# Nucleo_Mouse_SensorBoard_v2.net
KiCad netlist of a schematic drawn in EAGLE
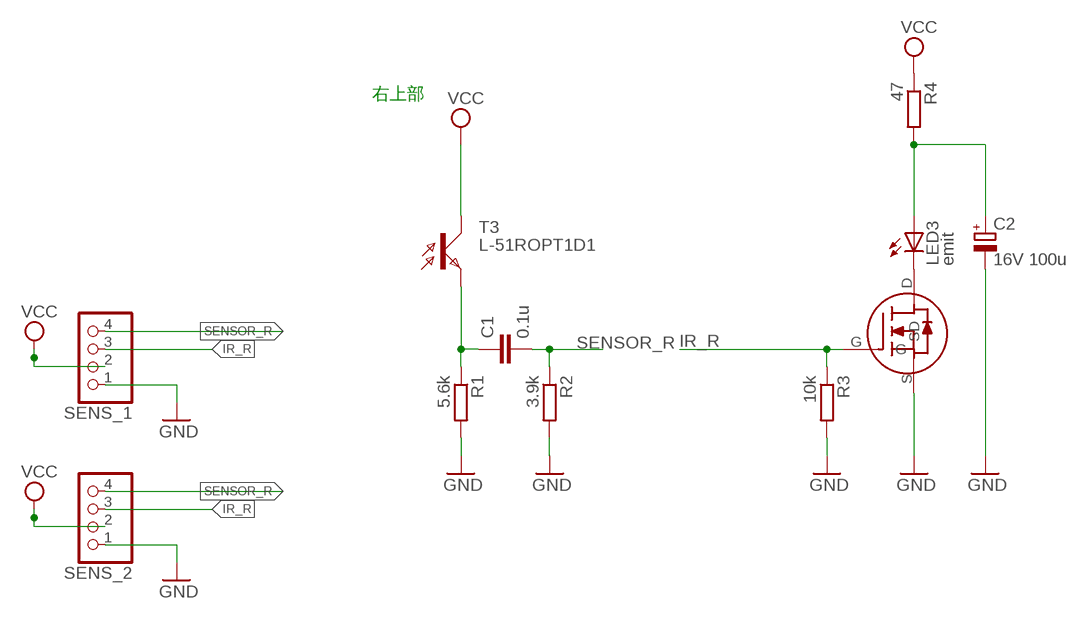
[diagram p0: schematic, sheet 1]

(export (version "E")
  (design (tool "Eeschema 10.0.6"))
  (components
    (comp (ref "2N2")
      (value "2N7000")
      (footprint "eagle-import:2N7000")
      (libsource (lib "eagle-import") (part "2N7000"))
    )
    (comp (ref "C1")
      (value "0.1u")
      (footprint "eagle-import:C2.5-3")
      (libsource (lib "eagle-import") (part "C2,5-3"))
    )
    (comp (ref "C2")
      (value "16V 100u")
      (footprint "eagle-import:E2-4")
      (libsource (lib "eagle-import") (part "CPOL-EUE2-4"))
    )
    (comp (ref "LED3")
      (value "emit")
      (footprint "eagle-import:LED5MM")
      (libsource (lib "eagle-import") (part "LED5MM"))
    )
    (comp (ref "R1")
      (value "5.6k")
      (footprint "eagle-import:0204_7")
      (libsource (lib "eagle-import") (part "R-EU_0204/7"))
    )
    (comp (ref "R2")
      (value "3.9k")
      (footprint "eagle-import:0204_7")
      (libsource (lib "eagle-import") (part "R-EU_0204/7"))
    )
    (comp (ref "R3")
      (value "10k")
      (footprint "eagle-import:0204_7")
      (libsource (lib "eagle-import") (part "R-EU_0204/7"))
    )
    (comp (ref "R4")
      (value "47")
      (footprint "eagle-import:0204_7")
      (libsource (lib "eagle-import") (part "R-EU_0204/7"))
    )
    (comp (ref "SENS_1")
      (value "TP-1X4")
      (footprint "eagle-import:1X04")
      (libsource (lib "eagle-import") (part "TP-1X4"))
    )
    (comp (ref "SENS_2")
      (value "TP-1X4")
      (footprint "eagle-import:1X04")
      (libsource (lib "eagle-import") (part "TP-1X4"))
    )
    (comp (ref "T3")
      (value "L-51ROPT1D1")
      (footprint "eagle-import:L-51ROPT1D1")
      (libsource (lib "eagle-import") (part "L-51ROPT1D1"))
    )
  )
  (nets
    (net (code "1") (name "GND") (class "Default")
      (node (ref "2N2") (pin "S") (pinfunction "S_S") (pintype "bidirectional"))
      (node (ref "C2") (pin "-") (pinfunction "-_-") (pintype "passive"))
      (node (ref "R1") (pin "2") (pinfunction "2_2") (pintype "passive"))
      (node (ref "R2") (pin "2") (pinfunction "2_2") (pintype "passive"))
      (node (ref "R3") (pin "2") (pinfunction "2_2") (pintype "passive"))
      (node (ref "SENS_1") (pin "1") (pinfunction "1_1") (pintype "passive"))
      (node (ref "SENS_2") (pin "1") (pinfunction "1_1") (pintype "passive"))
    )
    (net (code "2") (name "IR_R") (class "Default")
      (node (ref "2N2") (pin "G") (pinfunction "G_G") (pintype "bidirectional"))
      (node (ref "R3") (pin "1") (pinfunction "1_1") (pintype "passive"))
      (node (ref "SENS_1") (pin "3") (pinfunction "3_3") (pintype "passive"))
      (node (ref "SENS_2") (pin "3") (pinfunction "3_3") (pintype "passive"))
    )
    (net (code "3") (name "Net-(C2-Pad+)") (class "Default")
      (node (ref "C2") (pin "+") (pinfunction "+_+") (pintype "passive"))
      (node (ref "LED3") (pin "A") (pinfunction "A_A") (pintype "passive"))
      (node (ref "R4") (pin "2") (pinfunction "2_2") (pintype "passive"))
    )
    (net (code "4") (name "Net-(LED3-C)") (class "Default")
      (node (ref "2N2") (pin "D") (pinfunction "D_D") (pintype "bidirectional"))
      (node (ref "LED3") (pin "K") (pinfunction "C_K") (pintype "passive"))
    )
    (net (code "5") (name "Net-(T3-E)") (class "Default")
      (node (ref "C1") (pin "1") (pinfunction "1_1") (pintype "passive"))
      (node (ref "R1") (pin "1") (pinfunction "1_1") (pintype "passive"))
      (node (ref "T3") (pin "EMITTER") (pinfunction "E_EMITTER") (pintype "passive"))
    )
    (net (code "6") (name "SENSOR_R") (class "Default")
      (node (ref "C1") (pin "2") (pinfunction "2_2") (pintype "passive"))
      (node (ref "R2") (pin "1") (pinfunction "1_1") (pintype "passive"))
      (node (ref "SENS_1") (pin "4") (pinfunction "4_4") (pintype "passive"))
      (node (ref "SENS_2") (pin "4") (pinfunction "4_4") (pintype "passive"))
    )
    (net (code "7") (name "VCC") (class "Default")
      (node (ref "R4") (pin "1") (pinfunction "1_1") (pintype "passive"))
      (node (ref "SENS_1") (pin "2") (pinfunction "2_2") (pintype "passive"))
      (node (ref "SENS_2") (pin "2") (pinfunction "2_2") (pintype "passive"))
      (node (ref "T3") (pin "COLLECTOR") (pinfunction "C_COLLECTOR") (pintype "passive"))
    )
  )
)
